# Camera_IR.net
KiCad netlist of a schematic drawn in EasyEDA
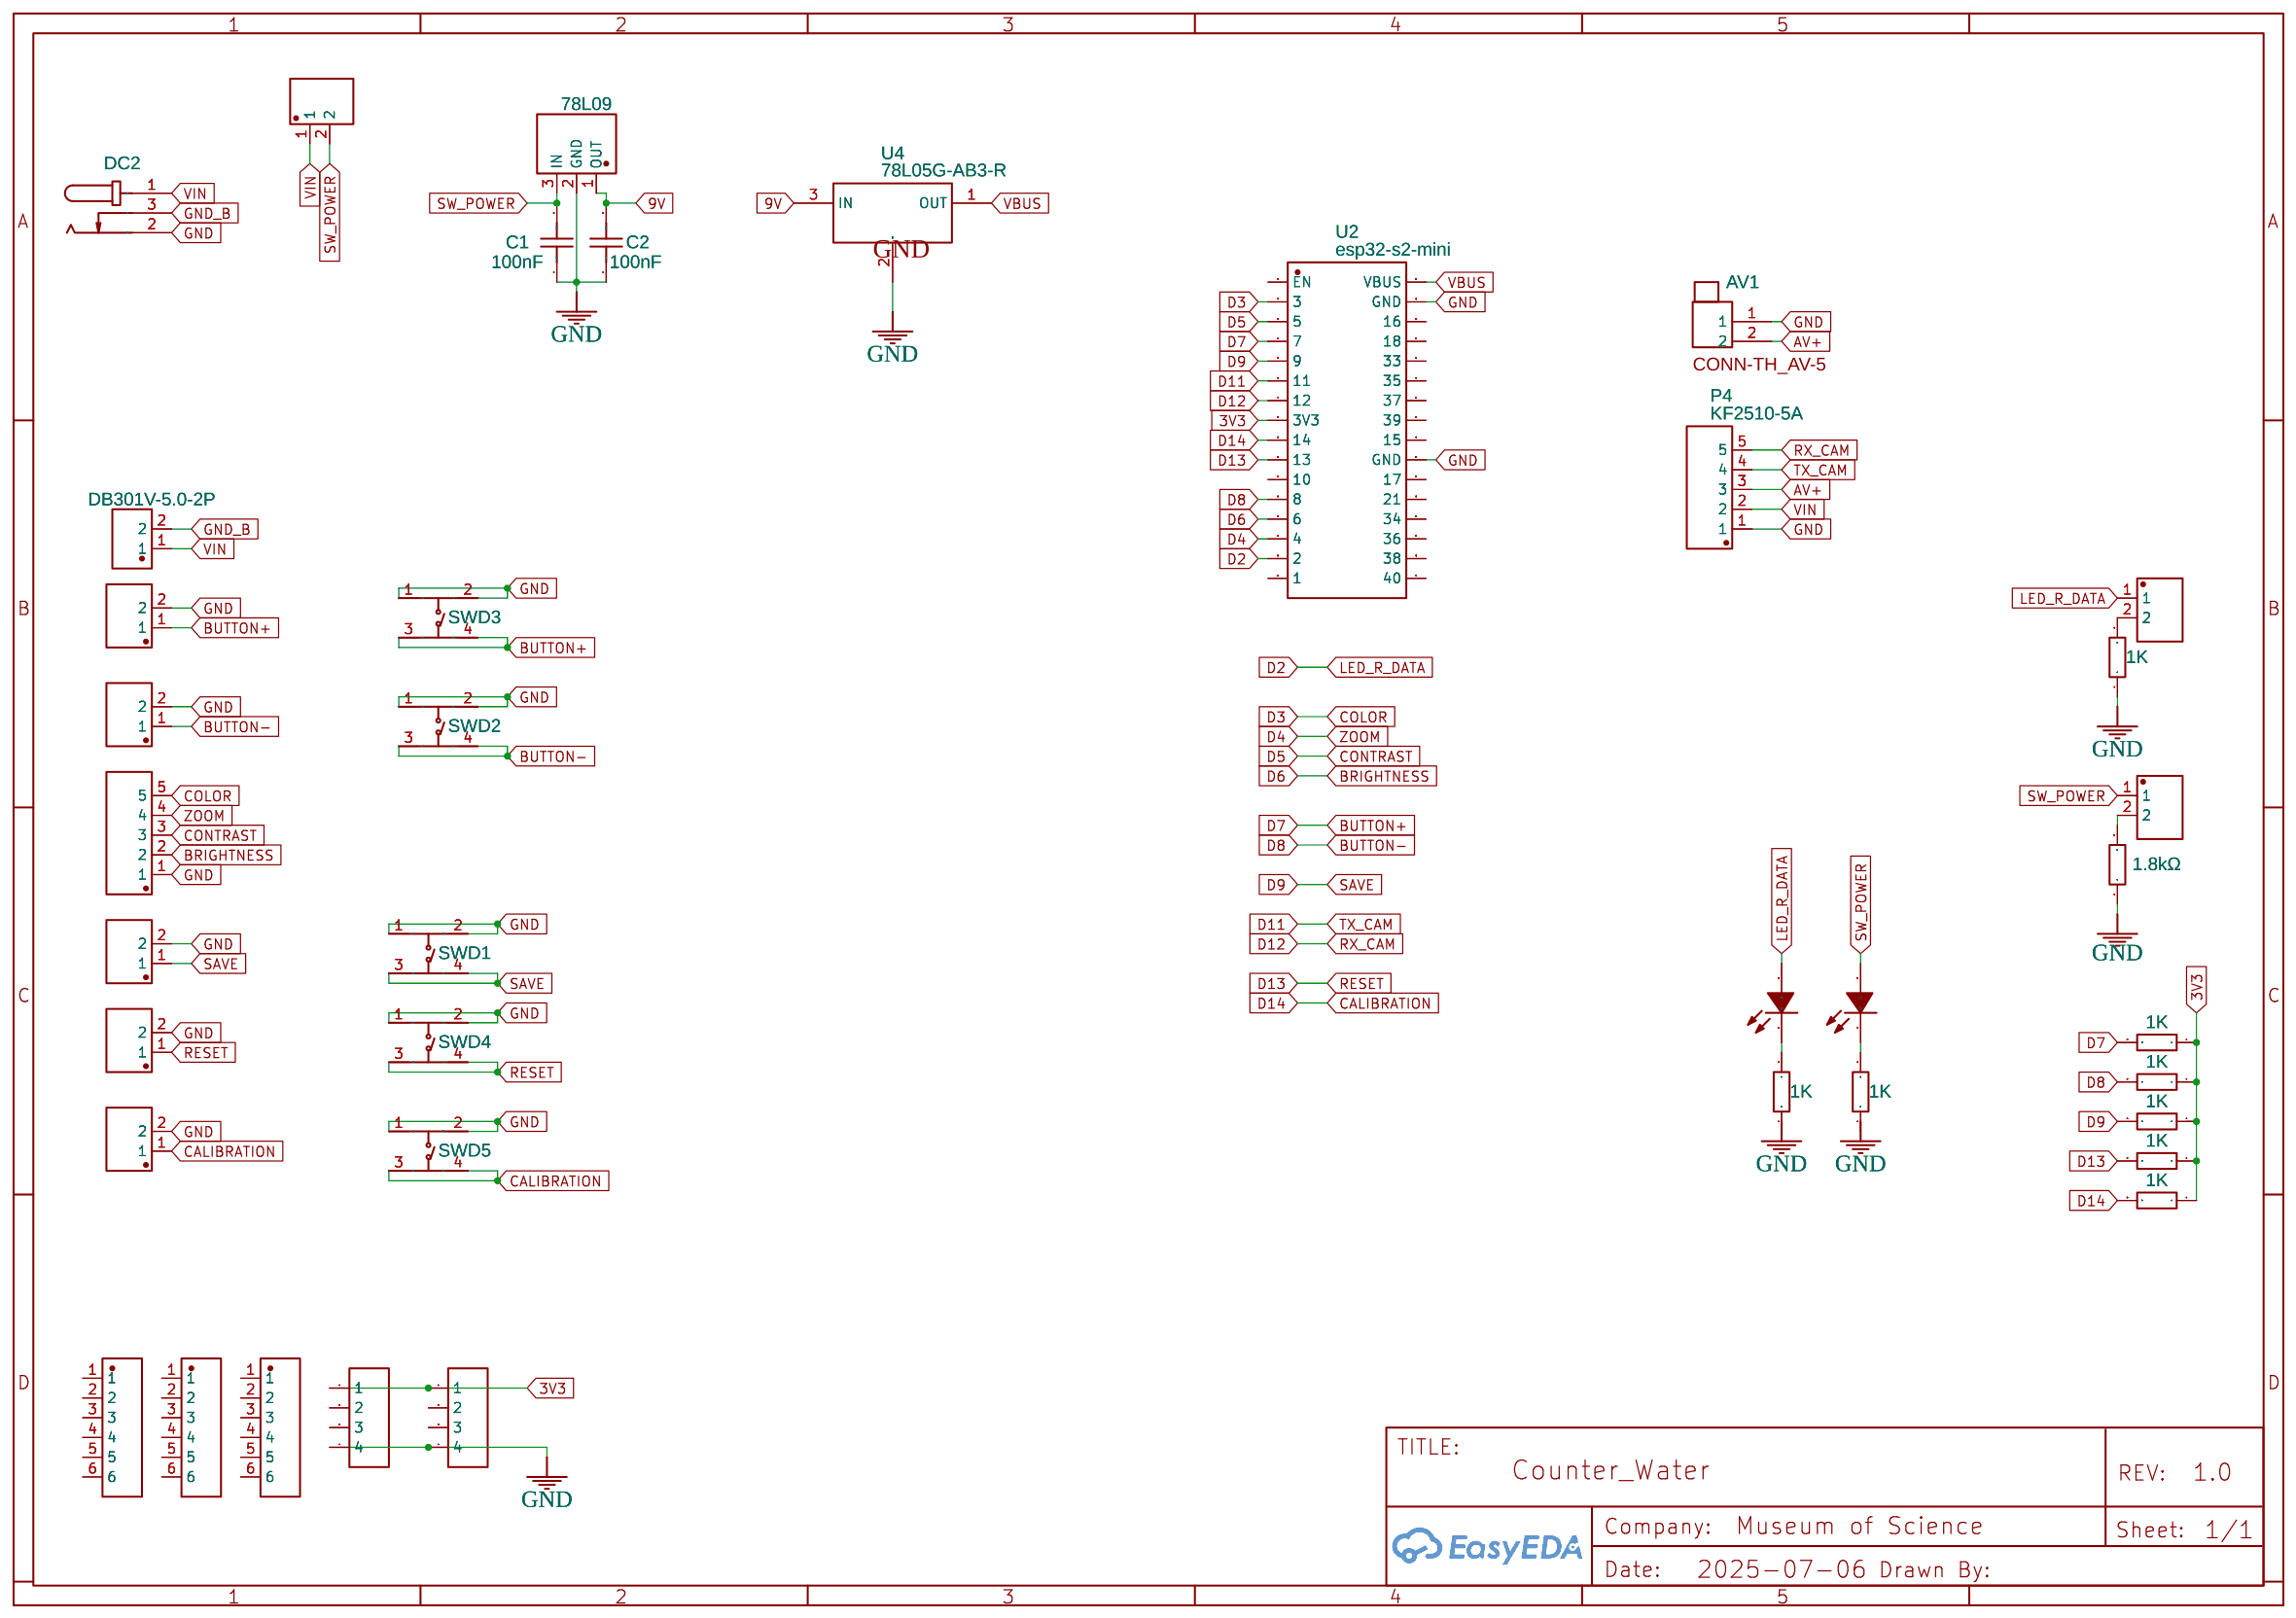
[diagram p0: schematic sheet]

(export (version "E")
  (design (tool "Eeschema 10.0.6"))
  (components
    (comp (ref "AV1")
      (value "AV-5")
      (fields (field (name "Manufacturer") "BOOMELE(博穆精密)"))
      (libsource (lib "") (part "AV-5"))
    )
    (comp (ref "C1")
      (value "100nF")
      (fields
        (field (name "Manufacturer Part") "CC0603KRX7R9BB104")
        (field (name "Manufacturer") "YAGEO(国巨)")
      )
      (libsource (lib "") (part "CC0603KRX7R9BB104"))
    )
    (comp (ref "C2")
      (value "100nF")
      (fields
        (field (name "Manufacturer Part") "CC0603KRX7R9BB104")
        (field (name "Manufacturer") "YAGEO(国巨)")
      )
      (libsource (lib "") (part "CC0603KRX7R9BB104"))
    )
    (comp (ref "D2")
      (value "LED_R_DATA")
      (fields (field (name "Manufacturer Part") "KF2510-2A") (field (name "Manufacturer") "BOOMELE"))
      (libsource (lib "") (part "KF2510-2A_3"))
    )
    (comp (ref "D7")
      (value "B+")
      (fields (field (name "Manufacturer Part") "KF2510-2A") (field (name "Manufacturer") "BOOMELE"))
      (libsource (lib "") (part "KF2510-2A_1"))
    )
    (comp (ref "D8")
      (value "B-")
      (fields (field (name "Manufacturer Part") "KF2510-2A") (field (name "Manufacturer") "BOOMELE"))
      (libsource (lib "") (part "KF2510-2A_1"))
    )
    (comp (ref "D9")
      (value "SAVE")
      (fields (field (name "Manufacturer Part") "KF2510-2A") (field (name "Manufacturer") "BOOMELE"))
      (libsource (lib "") (part "KF2510-2A_1"))
    )
    (comp (ref "D13")
      (value "RESET")
      (fields (field (name "Manufacturer Part") "KF2510-2A") (field (name "Manufacturer") "BOOMELE"))
      (libsource (lib "") (part "KF2510-2A_1"))
    )
    (comp (ref "D14")
      (value "FFC")
      (fields (field (name "Manufacturer Part") "KF2510-2A") (field (name "Manufacturer") "BOOMELE"))
      (libsource (lib "") (part "KF2510-2A_1"))
    )
    (comp (ref "DC2")
      (value "DC")
      (fields (field (name "Manufacturer Part") "DC005-2.0MM") (field (name "Manufacturer") "SOFNG"))
      (libsource (lib "") (part "DC005-2.0MM"))
    )
    (comp (ref "ERL1")
      (value "1K")
      (fields (field (name "Manufacturer Part") "0603WAF1001T5E") (field (name "Manufacturer") "UniOhm"))
      (libsource (lib "") (part "0603WAF1001T5E_1"))
    )
    (comp (ref "ERL2")
      (value "1K")
      (fields (field (name "Manufacturer Part") "0603WAF1001T5E") (field (name "Manufacturer") "UniOhm"))
      (libsource (lib "") (part "0603WAF1001T5E"))
    )
    (comp (ref "ERL4")
      (value "1K")
      (fields (field (name "Manufacturer Part") "0603WAF1001T5E") (field (name "Manufacturer") "UniOhm"))
      (libsource (lib "") (part "0603WAF1001T5E_1"))
    )
    (comp (ref "ERL5")
      (value "1K")
      (fields (field (name "Manufacturer Part") "0603WAF1001T5E") (field (name "Manufacturer") "UniOhm"))
      (libsource (lib "") (part "0603WAF1001T5E_1"))
    )
    (comp (ref "ERL6")
      (value "1K")
      (fields (field (name "Manufacturer Part") "0603WAF1001T5E") (field (name "Manufacturer") "UniOhm"))
      (libsource (lib "") (part "0603WAF1001T5E"))
    )
    (comp (ref "ERL9")
      (value "1K")
      (fields (field (name "Manufacturer Part") "0603WAF1001T5E") (field (name "Manufacturer") "UniOhm"))
      (libsource (lib "") (part "0603WAF1001T5E"))
    )
    (comp (ref "ERL11")
      (value "1K")
      (fields (field (name "Manufacturer Part") "0603WAF1001T5E") (field (name "Manufacturer") "UniOhm"))
      (libsource (lib "") (part "0603WAF1001T5E"))
    )
    (comp (ref "ERL12")
      (value "1K")
      (fields (field (name "Manufacturer Part") "0603WAF1001T5E") (field (name "Manufacturer") "UniOhm"))
      (libsource (lib "") (part "0603WAF1001T5E"))
    )
    (comp (ref "J6") (value "HDR-M-2.54_1x4") (libsource (lib "") (part "HDR-M-2.54_1x4")))
    (comp (ref "J7") (value "HDR-M-2.54_1x4") (libsource (lib "") (part "HDR-M-2.54_1x4")))
    (comp (ref "LED")
      (value "LED_POWER")
      (fields (field (name "Manufacturer Part") "KF2510-2A") (field (name "Manufacturer") "BOOMELE"))
      (libsource (lib "") (part "KF2510-2A_2"))
    )
    (comp (ref "LED4")
      (value "KT-0603R")
      (fields (field (name "Manufacturer") "KENTO"))
      (libsource (lib "") (part "KT-0603R"))
    )
    (comp (ref "LED5")
      (value "KT-0603R")
      (fields (field (name "Manufacturer") "KENTO"))
      (libsource (lib "") (part "KT-0603R"))
    )
    (comp (ref "P1")
      (value "KF2510-5A")
      (fields (field (name "Manufacturer Part") "2510-5A") (field (name "Manufacturer") "BOOMELE(博穆精密)"))
      (libsource (lib "") (part "KF2510-5A"))
    )
    (comp (ref "P2")
      (value "H6")
      (fields (field (name "Manufacturer Part") "2.54-1*6P母") (field (name "Manufacturer") "BOOMELE(博穆精密)"))
      (libsource (lib "") (part "Header-Female-2.54_1x6"))
    )
    (comp (ref "P3")
      (value "H6")
      (fields (field (name "Manufacturer Part") "2.54-1*6P母") (field (name "Manufacturer") "BOOMELE(博穆精密)"))
      (libsource (lib "") (part "Header-Female-2.54_1x6"))
    )
    (comp (ref "P4")
      (value "KF2510-5A")
      (fields (field (name "Manufacturer Part") "2510-5A") (field (name "Manufacturer") "BOOMELE(博穆精密)"))
      (libsource (lib "") (part "KF2510-5A"))
    )
    (comp (ref "P5")
      (value "H6")
      (fields (field (name "Manufacturer Part") "2.54-1*6P母") (field (name "Manufacturer") "BOOMELE(博穆精密)"))
      (libsource (lib "") (part "Header-Female-2.54_1x6"))
    )
    (comp (ref "R5")
      (value "1.8kΩ")
      (fields
        (field (name "Manufacturer Part") "0603WAF1801T5E")
        (field (name "Manufacturer") "UNI-ROYAL(厚声)")
      )
      (libsource (lib "") (part "0603WAF1801T5E"))
    )
    (comp (ref "SWD1")
      (value "TC-6610-7-160G")
      (fields (field (name "Manufacturer") "HCTL(华灿天禄)"))
      (libsource (lib "") (part "TC-6610-7-160G"))
    )
    (comp (ref "SWD2")
      (value "TC-6610-7-160G")
      (fields (field (name "Manufacturer") "HCTL(华灿天禄)"))
      (libsource (lib "") (part "TC-6610-7-160G"))
    )
    (comp (ref "SWD3")
      (value "TC-6610-7-160G")
      (fields (field (name "Manufacturer") "HCTL(华灿天禄)"))
      (libsource (lib "") (part "TC-6610-7-160G"))
    )
    (comp (ref "SWD4")
      (value "TC-6610-7-160G")
      (fields (field (name "Manufacturer") "HCTL(华灿天禄)"))
      (libsource (lib "") (part "TC-6610-7-160G"))
    )
    (comp (ref "SWD5")
      (value "TC-6610-7-160G")
      (fields (field (name "Manufacturer") "HCTL(华灿天禄)"))
      (libsource (lib "") (part "TC-6610-7-160G"))
    )
    (comp (ref "SW_P")
      (value "SW_P")
      (fields (field (name "Manufacturer Part") "KF2510-2A") (field (name "Manufacturer") "BOOMELE"))
      (libsource (lib "") (part "KF2510-2A"))
    )
    (comp (ref "U1")
      (value "78L09")
      (fields (field (name "Manufacturer") "CBI(创基)"))
      (libsource (lib "") (part "78L09U 78L09"))
    )
    (comp (ref "U2") (value "esp32-s2-mini") (libsource (lib "") (part "esp32-s2-mini")))
    (comp (ref "U3")
      (value "DB301V-5.0-2P")
      (fields
        (field (name "Manufacturer Part") "DB301V-5.0-2P-BU-S")
        (field (name "Manufacturer") "DORABO(地博电气)")
      )
      (libsource (lib "") (part "DB301V-5.0-2P"))
    )
    (comp (ref "U4")
      (value "78L05G-AB3-R")
      (fields (field (name "Manufacturer") "UTC(友顺)"))
      (libsource (lib "") (part "78L05G-AB3-R"))
    )
  )
  (nets
    (net (code "1") (name "3V3") (class "Default")
      (node (ref "ERL11") (pin "1") (pinfunction "1_1") (pintype "input"))
      (node (ref "ERL12") (pin "1") (pinfunction "1_1") (pintype "input"))
      (node (ref "ERL2") (pin "1") (pinfunction "1_1") (pintype "input"))
      (node (ref "ERL6") (pin "1") (pinfunction "1_1") (pintype "input"))
      (node (ref "ERL9") (pin "1") (pinfunction "1_1") (pintype "input"))
      (node (ref "J6") (pin "1") (pinfunction "1_1") (pintype "unspecified"))
      (node (ref "J7") (pin "1") (pinfunction "1_1") (pintype "unspecified"))
      (node (ref "U2") (pin "8") (pinfunction "3V3_8") (pintype "unspecified"))
    )
    (net (code "2") (name "9V") (class "Default")
      (node (ref "C2") (pin "2") (pinfunction "2_2") (pintype "unspecified"))
      (node (ref "U1") (pin "1") (pinfunction "OUT_1") (pintype "unspecified"))
      (node (ref "U4") (pin "3") (pinfunction "IN_3") (pintype "passive"))
    )
    (net (code "3") (name "AV+") (class "Default")
      (node (ref "AV1") (pin "2") (pinfunction "2_2") (pintype "unspecified"))
      (node (ref "P4") (pin "3") (pinfunction "3_3") (pintype "unspecified"))
    )
    (net (code "4") (name "BRIGHTNESS") (class "Default")
      (node (ref "P1") (pin "2") (pinfunction "2_2") (pintype "unspecified"))
      (node (ref "U2") (pin "13") (pinfunction "6_13") (pintype "unspecified"))
    )
    (net (code "5") (name "BUTTON+") (class "Default")
      (node (ref "D7") (pin "1") (pinfunction "1_1") (pintype "unspecified"))
      (node (ref "ERL6") (pin "2") (pinfunction "2_2") (pintype "input"))
      (node (ref "SWD3") (pin "3") (pinfunction "3_3") (pintype "unspecified"))
      (node (ref "SWD3") (pin "4") (pinfunction "4_4") (pintype "unspecified"))
      (node (ref "U2") (pin "4") (pinfunction "7_4") (pintype "unspecified"))
    )
    (net (code "6") (name "BUTTON-") (class "Default")
      (node (ref "D8") (pin "1") (pinfunction "1_1") (pintype "unspecified"))
      (node (ref "ERL11") (pin "2") (pinfunction "2_2") (pintype "input"))
      (node (ref "SWD2") (pin "3") (pinfunction "3_3") (pintype "unspecified"))
      (node (ref "SWD2") (pin "4") (pinfunction "4_4") (pintype "unspecified"))
      (node (ref "U2") (pin "12") (pinfunction "8_12") (pintype "unspecified"))
    )
    (net (code "7") (name "CALIBRATION") (class "Default")
      (node (ref "D14") (pin "1") (pinfunction "1_1") (pintype "unspecified"))
      (node (ref "ERL2") (pin "2") (pinfunction "2_2") (pintype "input"))
      (node (ref "SWD5") (pin "3") (pinfunction "3_3") (pintype "unspecified"))
      (node (ref "SWD5") (pin "4") (pinfunction "4_4") (pintype "unspecified"))
      (node (ref "U2") (pin "9") (pinfunction "14_9") (pintype "unspecified"))
    )
    (net (code "8") (name "COLOR") (class "Default")
      (node (ref "P1") (pin "5") (pinfunction "5_5") (pintype "unspecified"))
      (node (ref "U2") (pin "2") (pinfunction "3_2") (pintype "unspecified"))
    )
    (net (code "9") (name "CONTRAST") (class "Default")
      (node (ref "P1") (pin "3") (pinfunction "3_3") (pintype "unspecified"))
      (node (ref "U2") (pin "3") (pinfunction "5_3") (pintype "unspecified"))
    )
    (net (code "10") (name "D2") (class "Default")
      (node (ref "D2") (pin "1") (pinfunction "1_1") (pintype "unspecified"))
      (node (ref "LED5") (pin "2") (pinfunction "A_2") (pintype "unspecified"))
      (node (ref "U2") (pin "15") (pinfunction "2_15") (pintype "unspecified"))
    )
    (net (code "11") (name "D4") (class "Default")
      (node (ref "P1") (pin "4") (pinfunction "4_4") (pintype "unspecified"))
      (node (ref "U2") (pin "14") (pinfunction "4_14") (pintype "unspecified"))
    )
    (net (code "12") (name "D9") (class "Default")
      (node (ref "D9") (pin "1") (pinfunction "1_1") (pintype "unspecified"))
      (node (ref "ERL9") (pin "2") (pinfunction "2_2") (pintype "input"))
      (node (ref "SWD1") (pin "3") (pinfunction "3_3") (pintype "unspecified"))
      (node (ref "SWD1") (pin "4") (pinfunction "4_4") (pintype "unspecified"))
      (node (ref "U2") (pin "5") (pinfunction "9_5") (pintype "unspecified"))
    )
    (net (code "13") (name "D11") (class "Default")
      (node (ref "P4") (pin "4") (pinfunction "4_4") (pintype "unspecified"))
      (node (ref "U2") (pin "6") (pinfunction "11_6") (pintype "unspecified"))
    )
    (net (code "14") (name "D12") (class "Default")
      (node (ref "P4") (pin "5") (pinfunction "5_5") (pintype "unspecified"))
      (node (ref "U2") (pin "7") (pinfunction "12_7") (pintype "unspecified"))
    )
    (net (code "15") (name "D13") (class "Default")
      (node (ref "D13") (pin "1") (pinfunction "1_1") (pintype "unspecified"))
      (node (ref "ERL12") (pin "2") (pinfunction "2_2") (pintype "input"))
      (node (ref "SWD4") (pin "3") (pinfunction "3_3") (pintype "unspecified"))
      (node (ref "SWD4") (pin "4") (pinfunction "4_4") (pintype "unspecified"))
      (node (ref "U2") (pin "10") (pinfunction "13_10") (pintype "unspecified"))
    )
    (net (code "16") (name "GND") (class "Default")
      (node (ref "AV1") (pin "1") (pinfunction "1_1") (pintype "unspecified"))
      (node (ref "C1") (pin "1") (pinfunction "1_1") (pintype "unspecified"))
      (node (ref "C2") (pin "1") (pinfunction "1_1") (pintype "unspecified"))
      (node (ref "D13") (pin "2") (pinfunction "2_2") (pintype "unspecified"))
      (node (ref "D14") (pin "2") (pinfunction "2_2") (pintype "unspecified"))
      (node (ref "D7") (pin "2") (pinfunction "2_2") (pintype "unspecified"))
      (node (ref "D8") (pin "2") (pinfunction "2_2") (pintype "unspecified"))
      (node (ref "D9") (pin "2") (pinfunction "2_2") (pintype "unspecified"))
      (node (ref "DC2") (pin "2") (pinfunction "2_2") (pintype "unspecified"))
      (node (ref "ERL1") (pin "1") (pinfunction "1_1") (pintype "input"))
      (node (ref "ERL4") (pin "1") (pinfunction "1_1") (pintype "input"))
      (node (ref "ERL5") (pin "1") (pinfunction "1_1") (pintype "input"))
      (node (ref "J6") (pin "4") (pinfunction "4_4") (pintype "unspecified"))
      (node (ref "J7") (pin "4") (pinfunction "4_4") (pintype "unspecified"))
      (node (ref "P1") (pin "1") (pinfunction "1_1") (pintype "unspecified"))
      (node (ref "P4") (pin "1") (pinfunction "1_1") (pintype "unspecified"))
      (node (ref "R5") (pin "1") (pinfunction "1_1") (pintype "input"))
      (node (ref "SWD1") (pin "1") (pinfunction "1_1") (pintype "unspecified"))
      (node (ref "SWD1") (pin "2") (pinfunction "2_2") (pintype "unspecified"))
      (node (ref "SWD2") (pin "1") (pinfunction "1_1") (pintype "unspecified"))
      (node (ref "SWD2") (pin "2") (pinfunction "2_2") (pintype "unspecified"))
      (node (ref "SWD3") (pin "1") (pinfunction "1_1") (pintype "unspecified"))
      (node (ref "SWD3") (pin "2") (pinfunction "2_2") (pintype "unspecified"))
      (node (ref "SWD4") (pin "1") (pinfunction "1_1") (pintype "unspecified"))
      (node (ref "SWD4") (pin "2") (pinfunction "2_2") (pintype "unspecified"))
      (node (ref "SWD5") (pin "1") (pinfunction "1_1") (pintype "unspecified"))
      (node (ref "SWD5") (pin "2") (pinfunction "2_2") (pintype "unspecified"))
      (node (ref "U1") (pin "2") (pinfunction "GND_2") (pintype "unspecified"))
      (node (ref "U2") (pin "23") (pinfunction "GND_23") (pintype "unspecified"))
      (node (ref "U2") (pin "31") (pinfunction "GND_31") (pintype "unspecified"))
      (node (ref "U4") (pin "2") (pinfunction "GND_2") (pintype "passive"))
    )
    (net (code "17") (name "GND_B") (class "Default")
      (node (ref "DC2") (pin "3") (pinfunction "3_3") (pintype "unspecified"))
      (node (ref "U3") (pin "2") (pinfunction "2_2") (pintype "unspecified"))
    )
    (net (code "18") (name "Net-(D2-Pad2)") (class "Default")
      (node (ref "D2") (pin "2") (pinfunction "2_2") (pintype "unspecified"))
      (node (ref "ERL5") (pin "2") (pinfunction "2_2") (pintype "input"))
    )
    (net (code "19") (name "Net-(LED-Pad2)") (class "Default")
      (node (ref "LED") (pin "2") (pinfunction "2_2") (pintype "unspecified"))
      (node (ref "R5") (pin "2") (pinfunction "2_2") (pintype "input"))
    )
    (net (code "20") (name "Net-(LED4-K)") (class "Default")
      (node (ref "ERL4") (pin "2") (pinfunction "2_2") (pintype "input"))
      (node (ref "LED4") (pin "1") (pinfunction "K_1") (pintype "unspecified"))
    )
    (net (code "21") (name "Net-(LED5-K)") (class "Default")
      (node (ref "ERL1") (pin "2") (pinfunction "2_2") (pintype "input"))
      (node (ref "LED5") (pin "1") (pinfunction "K_1") (pintype "unspecified"))
    )
    (net (code "22") (name "SW_POWER") (class "Default")
      (node (ref "C1") (pin "2") (pinfunction "2_2") (pintype "unspecified"))
      (node (ref "LED") (pin "1") (pinfunction "1_1") (pintype "unspecified"))
      (node (ref "LED4") (pin "2") (pinfunction "A_2") (pintype "unspecified"))
      (node (ref "SW_P") (pin "2") (pinfunction "2_2") (pintype "unspecified"))
      (node (ref "U1") (pin "3") (pinfunction "IN_3") (pintype "unspecified"))
    )
    (net (code "23") (name "VBUS") (class "Default")
      (node (ref "U2") (pin "32") (pinfunction "VBUS_32") (pintype "unspecified"))
      (node (ref "U4") (pin "1") (pinfunction "OUT_1") (pintype "passive"))
    )
    (net (code "24") (name "VIN") (class "Default")
      (node (ref "DC2") (pin "1") (pinfunction "1_1") (pintype "unspecified"))
      (node (ref "P4") (pin "2") (pinfunction "2_2") (pintype "unspecified"))
      (node (ref "SW_P") (pin "1") (pinfunction "1_1") (pintype "unspecified"))
      (node (ref "U3") (pin "1") (pinfunction "1_1") (pintype "unspecified"))
    )
    (net (code "25") (name "unconnected-(J6-Pad2)") (class "Default")
      (node (ref "J6") (pin "2") (pinfunction "2_2") (pintype "unspecified"))
    )
    (net (code "26") (name "unconnected-(J6-Pad3)") (class "Default")
      (node (ref "J6") (pin "3") (pinfunction "3_3") (pintype "unspecified"))
    )
    (net (code "27") (name "unconnected-(J7-Pad2)") (class "Default")
      (node (ref "J7") (pin "2") (pinfunction "2_2") (pintype "unspecified"))
    )
    (net (code "28") (name "unconnected-(J7-Pad3)") (class "Default")
      (node (ref "J7") (pin "3") (pinfunction "3_3") (pintype "unspecified"))
    )
    (net (code "29") (name "unconnected-(P2-Pad1)") (class "Default")
      (node (ref "P2") (pin "1") (pinfunction "1_1") (pintype "unspecified"))
    )
    (net (code "30") (name "unconnected-(P2-Pad2)") (class "Default")
      (node (ref "P2") (pin "2") (pinfunction "2_2") (pintype "unspecified"))
    )
    (net (code "31") (name "unconnected-(P2-Pad3)") (class "Default")
      (node (ref "P2") (pin "3") (pinfunction "3_3") (pintype "unspecified"))
    )
    (net (code "32") (name "unconnected-(P2-Pad4)") (class "Default")
      (node (ref "P2") (pin "4") (pinfunction "4_4") (pintype "unspecified"))
    )
    (net (code "33") (name "unconnected-(P2-Pad5)") (class "Default")
      (node (ref "P2") (pin "5") (pinfunction "5_5") (pintype "unspecified"))
    )
    (net (code "34") (name "unconnected-(P2-Pad6)") (class "Default")
      (node (ref "P2") (pin "6") (pinfunction "6_6") (pintype "unspecified"))
    )
    (net (code "35") (name "unconnected-(P3-Pad1)") (class "Default")
      (node (ref "P3") (pin "1") (pinfunction "1_1") (pintype "unspecified"))
    )
    (net (code "36") (name "unconnected-(P3-Pad2)") (class "Default")
      (node (ref "P3") (pin "2") (pinfunction "2_2") (pintype "unspecified"))
    )
    (net (code "37") (name "unconnected-(P3-Pad3)") (class "Default")
      (node (ref "P3") (pin "3") (pinfunction "3_3") (pintype "unspecified"))
    )
    (net (code "38") (name "unconnected-(P3-Pad4)") (class "Default")
      (node (ref "P3") (pin "4") (pinfunction "4_4") (pintype "unspecified"))
    )
    (net (code "39") (name "unconnected-(P3-Pad5)") (class "Default")
      (node (ref "P3") (pin "5") (pinfunction "5_5") (pintype "unspecified"))
    )
    (net (code "40") (name "unconnected-(P3-Pad6)") (class "Default")
      (node (ref "P3") (pin "6") (pinfunction "6_6") (pintype "unspecified"))
    )
    (net (code "41") (name "unconnected-(P5-Pad1)") (class "Default")
      (node (ref "P5") (pin "1") (pinfunction "1_1") (pintype "unspecified"))
    )
    (net (code "42") (name "unconnected-(P5-Pad2)") (class "Default")
      (node (ref "P5") (pin "2") (pinfunction "2_2") (pintype "unspecified"))
    )
    (net (code "43") (name "unconnected-(P5-Pad3)") (class "Default")
      (node (ref "P5") (pin "3") (pinfunction "3_3") (pintype "unspecified"))
    )
    (net (code "44") (name "unconnected-(P5-Pad4)") (class "Default")
      (node (ref "P5") (pin "4") (pinfunction "4_4") (pintype "unspecified"))
    )
    (net (code "45") (name "unconnected-(P5-Pad5)") (class "Default")
      (node (ref "P5") (pin "5") (pinfunction "5_5") (pintype "unspecified"))
    )
    (net (code "46") (name "unconnected-(P5-Pad6)") (class "Default")
      (node (ref "P5") (pin "6") (pinfunction "6_6") (pintype "unspecified"))
    )
    (net (code "47") (name "unconnected-(U2-1-Pad16)") (class "Default")
      (node (ref "U2") (pin "16") (pinfunction "1_16") (pintype "unspecified"))
    )
    (net (code "48") (name "unconnected-(U2-10-Pad11)") (class "Default")
      (node (ref "U2") (pin "11") (pinfunction "10_11") (pintype "unspecified"))
    )
    (net (code "49") (name "unconnected-(U2-15-Pad24)") (class "Default")
      (node (ref "U2") (pin "24") (pinfunction "15_24") (pintype "unspecified"))
    )
    (net (code "50") (name "unconnected-(U2-16-Pad30)") (class "Default")
      (node (ref "U2") (pin "30") (pinfunction "16_30") (pintype "unspecified"))
    )
    (net (code "51") (name "unconnected-(U2-17-Pad22)") (class "Default")
      (node (ref "U2") (pin "22") (pinfunction "17_22") (pintype "unspecified"))
    )
    (net (code "52") (name "unconnected-(U2-18-Pad29)") (class "Default")
      (node (ref "U2") (pin "29") (pinfunction "18_29") (pintype "unspecified"))
    )
    (net (code "53") (name "unconnected-(U2-33-Pad28)") (class "Default")
      (node (ref "U2") (pin "28") (pinfunction "33_28") (pintype "unspecified"))
    )
    (net (code "54") (name "unconnected-(U2-34-Pad20)") (class "Default")
      (node (ref "U2") (pin "20") (pinfunction "34_20") (pintype "unspecified"))
    )
    (net (code "55") (name "unconnected-(U2-35-Pad27)") (class "Default")
      (node (ref "U2") (pin "27") (pinfunction "35_27") (pintype "unspecified"))
    )
    (net (code "56") (name "unconnected-(U2-36-Pad19)") (class "Default")
      (node (ref "U2") (pin "19") (pinfunction "36_19") (pintype "unspecified"))
    )
    (net (code "57") (name "unconnected-(U2-37-Pad26)") (class "Default")
      (node (ref "U2") (pin "26") (pinfunction "37_26") (pintype "unspecified"))
    )
    (net (code "58") (name "unconnected-(U2-38-Pad18)") (class "Default")
      (node (ref "U2") (pin "18") (pinfunction "38_18") (pintype "unspecified"))
    )
    (net (code "59") (name "unconnected-(U2-39-Pad25)") (class "Default")
      (node (ref "U2") (pin "25") (pinfunction "39_25") (pintype "unspecified"))
    )
    (net (code "60") (name "unconnected-(U2-40-Pad17)") (class "Default")
      (node (ref "U2") (pin "17") (pinfunction "40_17") (pintype "unspecified"))
    )
    (net (code "61") (name "unconnected-(U2-EN-Pad1)") (class "Default")
      (node (ref "U2") (pin "1") (pinfunction "EN_1") (pintype "unspecified"))
    )
    (net (code "62") (name "unconnected-(U2-Pad21)") (class "Default")
      (node (ref "U2") (pin "21") (pinfunction "21_21") (pintype "unspecified"))
    )
  )
)
